# L3DCube_6x6x6_LED_Stick_Rev1_2.net
KiCad netlist of a schematic drawn in EAGLE
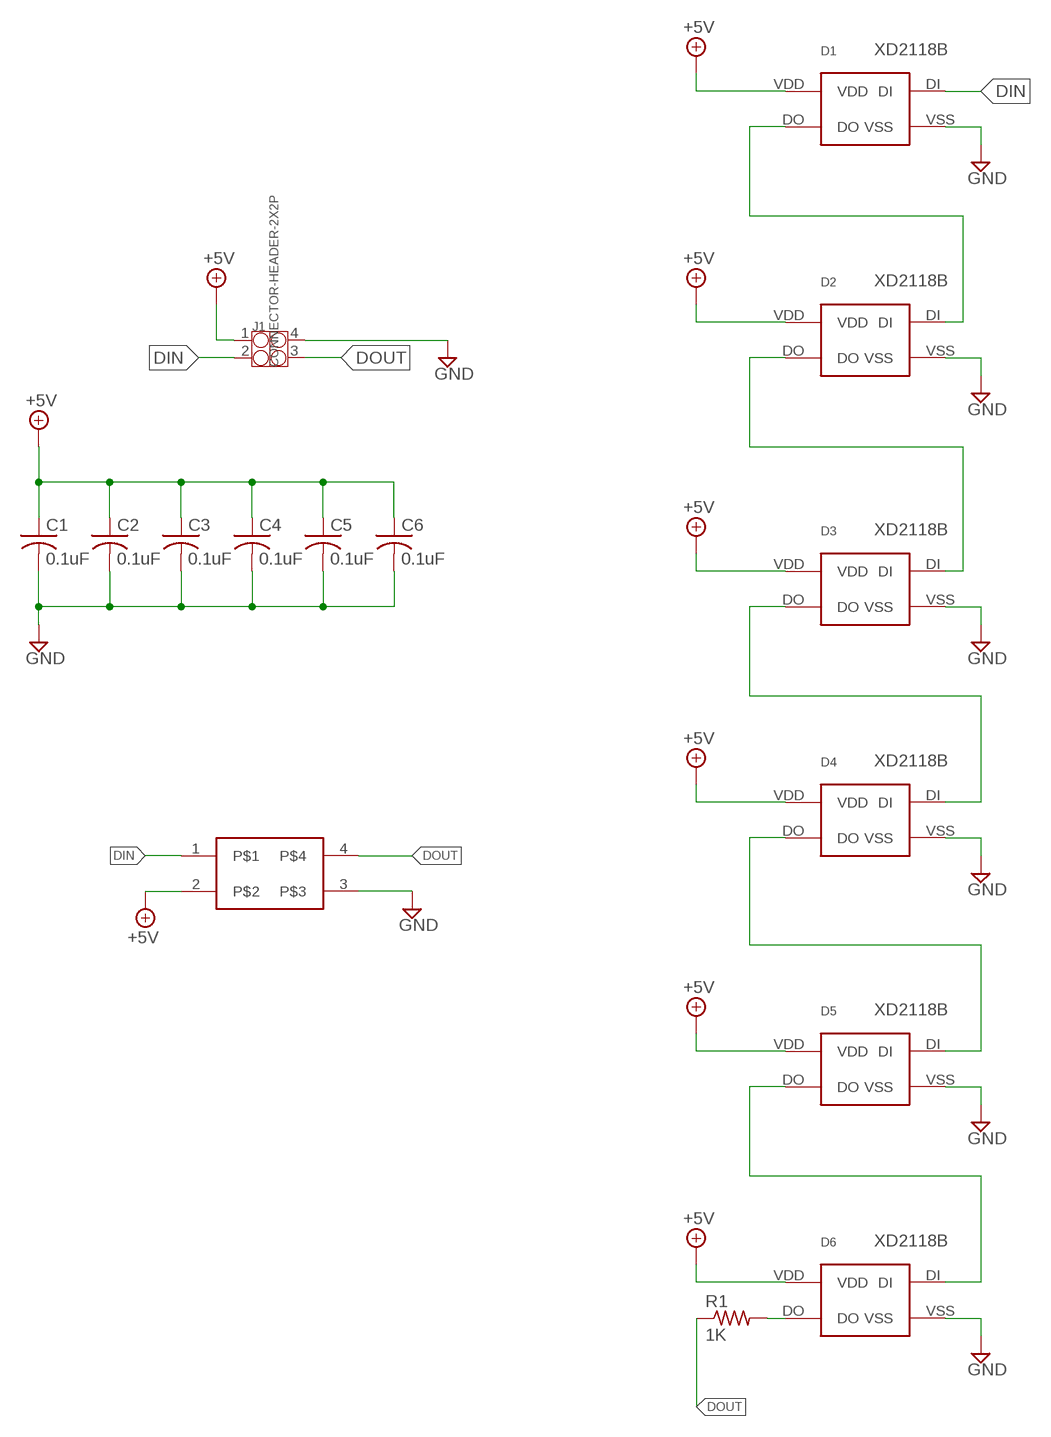
[diagram p0: schematic, sheet 1]

(export (version "E")
  (design (tool "Eeschema 10.0.6"))
  (components
    (comp (ref "C1")
      (value "0.1uF")
      (footprint "eagle-import:C0402")
      (libsource (lib "eagle-import") (part "C-USC0402"))
    )
    (comp (ref "C2")
      (value "0.1uF")
      (footprint "eagle-import:C0402")
      (libsource (lib "eagle-import") (part "C-USC0402"))
    )
    (comp (ref "C3")
      (value "0.1uF")
      (footprint "eagle-import:C0402")
      (libsource (lib "eagle-import") (part "C-USC0402"))
    )
    (comp (ref "C4")
      (value "0.1uF")
      (footprint "eagle-import:C0402")
      (libsource (lib "eagle-import") (part "C-USC0402"))
    )
    (comp (ref "C5")
      (value "0.1uF")
      (footprint "eagle-import:C0402")
      (libsource (lib "eagle-import") (part "C-USC0402"))
    )
    (comp (ref "C6")
      (value "0.1uF")
      (footprint "eagle-import:C0402")
      (libsource (lib "eagle-import") (part "C-USC0402"))
    )
    (comp (ref "D1")
      (value "XD2118B")
      (footprint "eagle-import:WS2812B")
      (libsource (lib "eagle-import") (part "WS2812B"))
    )
    (comp (ref "D2")
      (value "XD2118B")
      (footprint "eagle-import:WS2812B")
      (libsource (lib "eagle-import") (part "WS2812B"))
    )
    (comp (ref "D3")
      (value "XD2118B")
      (footprint "eagle-import:WS2812B")
      (libsource (lib "eagle-import") (part "WS2812B"))
    )
    (comp (ref "D4")
      (value "XD2118B")
      (footprint "eagle-import:WS2812B")
      (libsource (lib "eagle-import") (part "WS2812B"))
    )
    (comp (ref "D5")
      (value "XD2118B")
      (footprint "eagle-import:WS2812B")
      (libsource (lib "eagle-import") (part "WS2812B"))
    )
    (comp (ref "D6")
      (value "XD2118B")
      (footprint "eagle-import:WS2812B")
      (libsource (lib "eagle-import") (part "WS2812B"))
    )
    (comp (ref "J1")
      (value "CONNECTOR-HEADER-2X2P")
      (footprint "eagle-import:2X2P-2.54")
      (libsource (lib "eagle-import") (part "CONNECTOR-HEADER-2X2P"))
    )
    (comp (ref "R1")
      (value "1K")
      (footprint "eagle-import:R0402")
      (libsource (lib "eagle-import") (part "R-US_R0402"))
    )
    (comp (ref "U$1")
      (value "TESTPAD-2X2-2.54")
      (footprint "eagle-import:2X2P-2.54-TESTPAD")
      (libsource (lib "eagle-import") (part "TESTPAD-2X2-2.54"))
    )
  )
  (nets
    (net (code "1") (name "+5V") (class "Default")
      (node (ref "C1") (pin "1") (pinfunction "1_1") (pintype "passive"))
      (node (ref "C2") (pin "1") (pinfunction "1_1") (pintype "passive"))
      (node (ref "C3") (pin "1") (pinfunction "1_1") (pintype "passive"))
      (node (ref "C4") (pin "1") (pinfunction "1_1") (pintype "passive"))
      (node (ref "C5") (pin "1") (pinfunction "1_1") (pintype "passive"))
      (node (ref "C6") (pin "1") (pinfunction "1_1") (pintype "passive"))
      (node (ref "D1") (pin "VDD") (pinfunction "VDD_VDD") (pintype "bidirectional"))
      (node (ref "D2") (pin "VDD") (pinfunction "VDD_VDD") (pintype "bidirectional"))
      (node (ref "D3") (pin "VDD") (pinfunction "VDD_VDD") (pintype "bidirectional"))
      (node (ref "D4") (pin "VDD") (pinfunction "VDD_VDD") (pintype "bidirectional"))
      (node (ref "D5") (pin "VDD") (pinfunction "VDD_VDD") (pintype "bidirectional"))
      (node (ref "D6") (pin "VDD") (pinfunction "VDD_VDD") (pintype "bidirectional"))
      (node (ref "J1") (pin "1") (pinfunction "1_1") (pintype "bidirectional"))
      (node (ref "U$1") (pin "2") (pinfunction "P$2_2") (pintype "bidirectional"))
    )
    (net (code "2") (name "DIN") (class "Default")
      (node (ref "D1") (pin "DI") (pinfunction "DI_DI") (pintype "bidirectional"))
      (node (ref "J1") (pin "2") (pinfunction "2_2") (pintype "bidirectional"))
      (node (ref "U$1") (pin "1") (pinfunction "P$1_1") (pintype "bidirectional"))
    )
    (net (code "3") (name "DOUT") (class "Default")
      (node (ref "J1") (pin "3") (pinfunction "3_3") (pintype "bidirectional"))
      (node (ref "R1") (pin "1") (pinfunction "1_1") (pintype "passive"))
      (node (ref "U$1") (pin "4") (pinfunction "P$4_4") (pintype "bidirectional"))
    )
    (net (code "4") (name "GND") (class "Default")
      (node (ref "C1") (pin "2") (pinfunction "2_2") (pintype "passive"))
      (node (ref "C2") (pin "2") (pinfunction "2_2") (pintype "passive"))
      (node (ref "C3") (pin "2") (pinfunction "2_2") (pintype "passive"))
      (node (ref "C4") (pin "2") (pinfunction "2_2") (pintype "passive"))
      (node (ref "C5") (pin "2") (pinfunction "2_2") (pintype "passive"))
      (node (ref "C6") (pin "2") (pinfunction "2_2") (pintype "passive"))
      (node (ref "D1") (pin "VSS") (pinfunction "VSS_VSS") (pintype "bidirectional"))
      (node (ref "D2") (pin "VSS") (pinfunction "VSS_VSS") (pintype "bidirectional"))
      (node (ref "D3") (pin "VSS") (pinfunction "VSS_VSS") (pintype "bidirectional"))
      (node (ref "D4") (pin "VSS") (pinfunction "VSS_VSS") (pintype "bidirectional"))
      (node (ref "D5") (pin "VSS") (pinfunction "VSS_VSS") (pintype "bidirectional"))
      (node (ref "D6") (pin "VSS") (pinfunction "VSS_VSS") (pintype "bidirectional"))
      (node (ref "J1") (pin "4") (pinfunction "4_4") (pintype "bidirectional"))
      (node (ref "U$1") (pin "3") (pinfunction "P$3_3") (pintype "bidirectional"))
    )
    (net (code "5") (name "Net-(D1-PadDO)") (class "Default")
      (node (ref "D1") (pin "DO") (pinfunction "DO_DO") (pintype "bidirectional"))
      (node (ref "D2") (pin "DI") (pinfunction "DI_DI") (pintype "bidirectional"))
    )
    (net (code "6") (name "Net-(D2-PadDO)") (class "Default")
      (node (ref "D2") (pin "DO") (pinfunction "DO_DO") (pintype "bidirectional"))
      (node (ref "D3") (pin "DI") (pinfunction "DI_DI") (pintype "bidirectional"))
    )
    (net (code "7") (name "Net-(D3-PadDO)") (class "Default")
      (node (ref "D3") (pin "DO") (pinfunction "DO_DO") (pintype "bidirectional"))
      (node (ref "D4") (pin "DI") (pinfunction "DI_DI") (pintype "bidirectional"))
    )
    (net (code "8") (name "Net-(D4-PadDO)") (class "Default")
      (node (ref "D4") (pin "DO") (pinfunction "DO_DO") (pintype "bidirectional"))
      (node (ref "D5") (pin "DI") (pinfunction "DI_DI") (pintype "bidirectional"))
    )
    (net (code "9") (name "Net-(D5-PadDO)") (class "Default")
      (node (ref "D5") (pin "DO") (pinfunction "DO_DO") (pintype "bidirectional"))
      (node (ref "D6") (pin "DI") (pinfunction "DI_DI") (pintype "bidirectional"))
    )
    (net (code "10") (name "Net-(D6-PadDO)") (class "Default")
      (node (ref "D6") (pin "DO") (pinfunction "DO_DO") (pintype "bidirectional"))
      (node (ref "R1") (pin "2") (pinfunction "2_2") (pintype "passive"))
    )
  )
)
